# Sheet1.net
KiCad netlist of a schematic drawn in Altium Designer
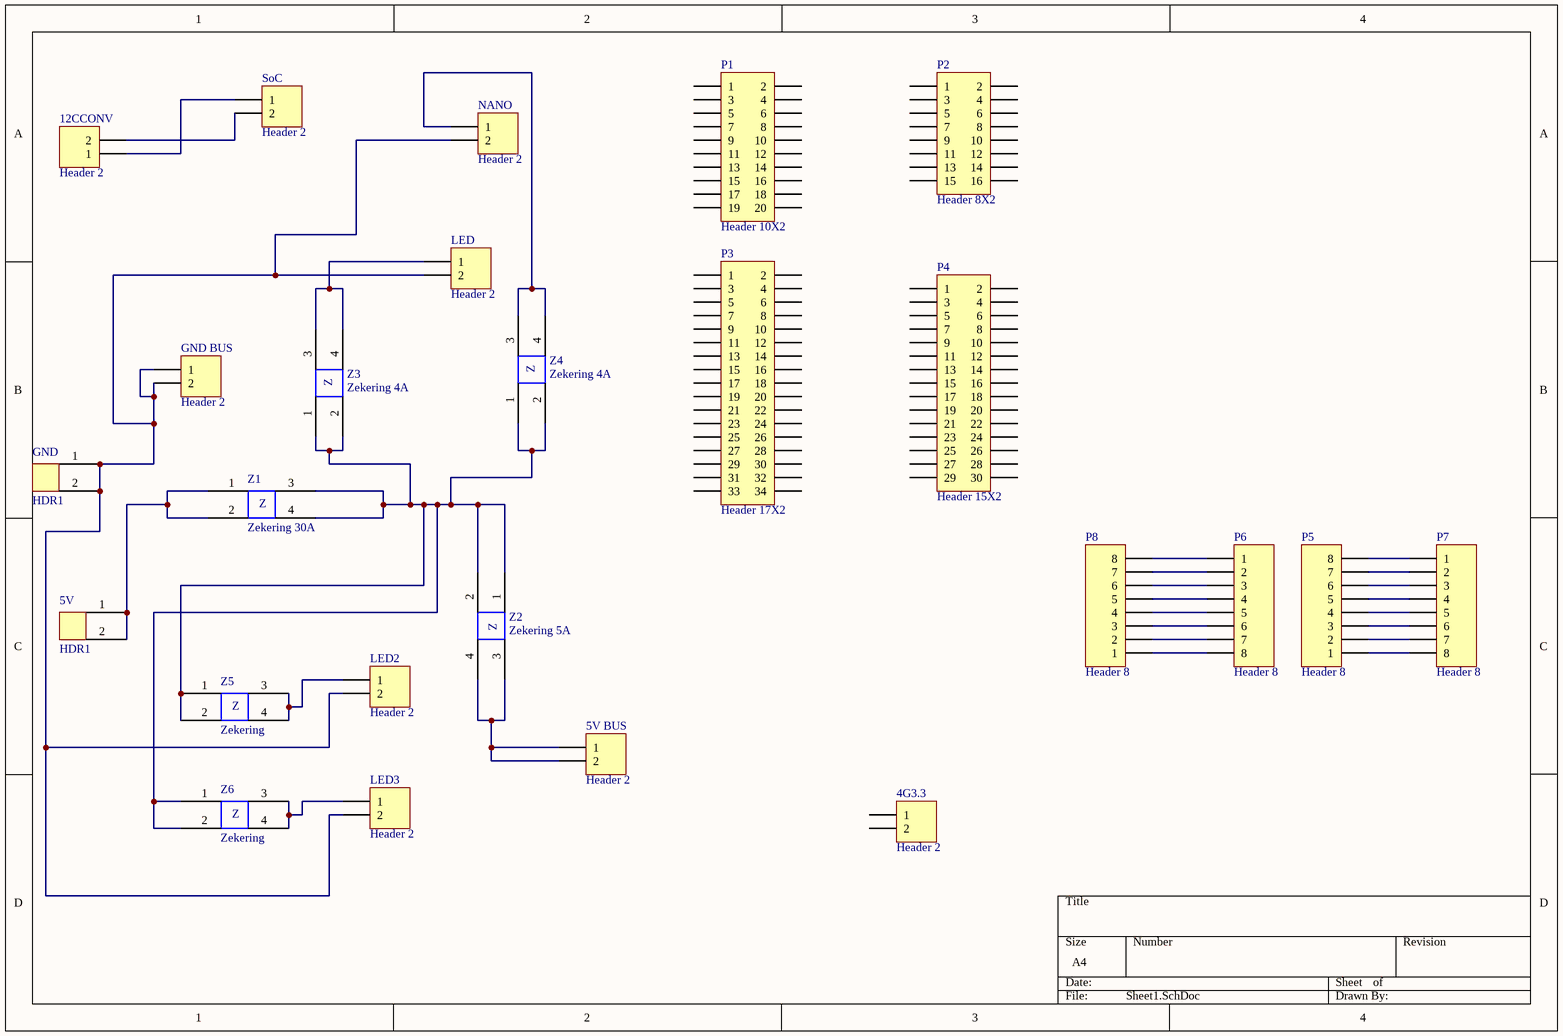
[diagram p0: Sheet1.SchDoc]

(export (version "E")
  (design (tool "Eeschema 10.0.6"))
  (components
    (comp (ref "4G3.3")
      (value "Header 2")
      (footprint "HDR1X2")
      (description "Header, 2-Pin")
      (fields (field (name "PUBLISHER") "Altium Limited"))
      (libsource (lib "Miscellaneous Connectors") (part "Header 2"))
    )
    (comp (ref "5V") (value "HDR1") (footprint "HDR1") (libsource (lib "Schlib1") (part "HDR1")))
    (comp (ref "5V BUS")
      (value "Header 2")
      (footprint "HDR2")
      (description "Header, 2-Pin")
      (fields (field (name "PUBLISHER") "Altium Limited"))
      (libsource (lib "Miscellaneous Connectors") (part "Header 2"))
    )
    (comp (ref "12CCONV")
      (value "Header 2")
      (footprint "HDR1X2")
      (description "Header, 2-Pin")
      (fields (field (name "PUBLISHER") "Altium Limited"))
      (libsource (lib "") (part "Header 2_1"))
    )
    (comp (ref "GND") (value "HDR1") (footprint "HDR1") (libsource (lib "Schlib1") (part "HDR1")))
    (comp (ref "GND BUS")
      (value "Header 2")
      (footprint "HDR2")
      (description "Header, 2-Pin")
      (fields (field (name "PUBLISHER") "Altium Limited"))
      (libsource (lib "Miscellaneous Connectors") (part "Header 2"))
    )
    (comp (ref "LED")
      (value "Header 2")
      (footprint "HDR2")
      (description "Header, 2-Pin")
      (fields (field (name "PUBLISHER") "Altium Limited"))
      (libsource (lib "Miscellaneous Connectors") (part "Header 2"))
    )
    (comp (ref "LED2")
      (value "Header 2")
      (footprint "HDR2")
      (description "Header, 2-Pin")
      (fields (field (name "PUBLISHER") "Altium Limited"))
      (libsource (lib "Miscellaneous Connectors") (part "Header 2"))
    )
    (comp (ref "LED3")
      (value "Header 2")
      (footprint "HDR2")
      (description "Header, 2-Pin")
      (fields (field (name "PUBLISHER") "Altium Limited"))
      (libsource (lib "Miscellaneous Connectors") (part "Header 2"))
    )
    (comp (ref "NANO")
      (value "Header 2")
      (footprint "HDR1X2")
      (description "Header, 2-Pin")
      (fields (field (name "PUBLISHER") "Altium Limited"))
      (libsource (lib "Miscellaneous Connectors") (part "Header 2"))
    )
    (comp (ref "P1")
      (value "Header 10X2")
      (footprint "hdr10x2")
      (description "Header, 10-Pin, Dual row")
      (fields (field (name "PUBLISHER") "Altium Limited"))
      (libsource (lib "Miscellaneous Connectors") (part "Header 10X2"))
    )
    (comp (ref "P2")
      (value "Header 8X2")
      (footprint "hdr8x2")
      (description "Header, 8-Pin, Dual row")
      (fields (field (name "PUBLISHER") "Altium Limited"))
      (libsource (lib "Miscellaneous Connectors") (part "Header 8X2"))
    )
    (comp (ref "P3")
      (value "Header 17X2")
      (footprint "hdr17x2")
      (description "Header, 17-Pin, Dual row")
      (fields (field (name "PUBLISHER") "Altium Limited"))
      (libsource (lib "Miscellaneous Connectors") (part "Header 17X2"))
    )
    (comp (ref "P4")
      (value "Header 15X2")
      (footprint "hdr15x2")
      (description "Header, 15-Pin, Dual row")
      (fields (field (name "PUBLISHER") "Altium Limited"))
      (libsource (lib "Miscellaneous Connectors") (part "Header 15X2"))
    )
    (comp (ref "P5")
      (value "Header 8")
      (footprint "HDR8")
      (description "Header, 8-Pin")
      (fields (field (name "PUBLISHER") "Altium Limited"))
      (libsource (lib "") (part "Header 8_1"))
    )
    (comp (ref "P6")
      (value "Header 8")
      (footprint "HDR8")
      (description "Header, 8-Pin")
      (fields (field (name "PUBLISHER") "Altium Limited"))
      (libsource (lib "Miscellaneous Connectors") (part "Header 8"))
    )
    (comp (ref "P7")
      (value "Header 8")
      (footprint "HDR8")
      (description "Header, 8-Pin")
      (fields (field (name "PUBLISHER") "Altium Limited"))
      (libsource (lib "Miscellaneous Connectors") (part "Header 8"))
    )
    (comp (ref "P8")
      (value "Header 8")
      (footprint "HDR8")
      (description "Header, 8-Pin")
      (fields (field (name "PUBLISHER") "Altium Limited"))
      (libsource (lib "") (part "Header 8_1"))
    )
    (comp (ref "SoC")
      (value "Header 2")
      (footprint "HDR1X2")
      (description "Header, 2-Pin")
      (fields (field (name "PUBLISHER") "Altium Limited"))
      (libsource (lib "Miscellaneous Connectors") (part "Header 2"))
    )
    (comp (ref "Z1")
      (value "Zekering 30A")
      (footprint "Zekering")
      (libsource (lib "Schlib1") (part "Zekering"))
    )
    (comp (ref "Z2")
      (value "Zekering 5A")
      (footprint "Zekering")
      (libsource (lib "Schlib1") (part "Zekering"))
    )
    (comp (ref "Z3")
      (value "Zekering 4A")
      (footprint "Zekering")
      (libsource (lib "Schlib1") (part "Zekering"))
    )
    (comp (ref "Z4")
      (value "Zekering 4A")
      (footprint "Zekering")
      (libsource (lib "Schlib1") (part "Zekering"))
    )
    (comp (ref "Z5") (value "Zekering") (footprint "Zekering") (libsource (lib "Schlib1") (part "Zekering")))
    (comp (ref "Z6") (value "Zekering") (footprint "Zekering") (libsource (lib "Schlib1") (part "Zekering")))
  )
  (nets
    (net (code "1") (name "Net-(5V-8)") (class "Default")
      (node (ref "5V") (pin "1") (pinfunction "8_1") (pintype "passive"))
      (node (ref "5V") (pin "2") (pinfunction "2_2") (pintype "passive"))
      (node (ref "Z1") (pin "1") (pinfunction "3_1") (pintype "passive"))
      (node (ref "Z1") (pin "2") (pinfunction "4_2") (pintype "passive"))
    )
    (net (code "2") (name "Net-(12CCONV-Pad1)") (class "Default")
      (node (ref "12CCONV") (pin "1") (pinfunction "1_1") (pintype "passive"))
      (node (ref "SoC") (pin "1") (pinfunction "1_1") (pintype "passive"))
    )
    (net (code "3") (name "Net-(12CCONV-Pad2)") (class "Default")
      (node (ref "12CCONV") (pin "2") (pinfunction "2_2") (pintype "passive"))
      (node (ref "SoC") (pin "2") (pinfunction "2_2") (pintype "passive"))
    )
    (net (code "4") (name "Net-(GND-8)") (class "Default")
      (node (ref "GND") (pin "1") (pinfunction "8_1") (pintype "passive"))
      (node (ref "GND") (pin "2") (pinfunction "2_2") (pintype "passive"))
      (node (ref "GND BUS") (pin "1") (pinfunction "1_1") (pintype "passive"))
      (node (ref "GND BUS") (pin "2") (pinfunction "2_2") (pintype "passive"))
      (node (ref "LED") (pin "2") (pinfunction "2_2") (pintype "passive"))
      (node (ref "LED2") (pin "2") (pinfunction "2_2") (pintype "passive"))
      (node (ref "LED3") (pin "2") (pinfunction "2_2") (pintype "passive"))
      (node (ref "NANO") (pin "2") (pinfunction "2_2") (pintype "passive"))
    )
    (net (code "5") (name "Net-(P5-Pad1)") (class "Default")
      (node (ref "P5") (pin "1") (pinfunction "1_1") (pintype "passive"))
      (node (ref "P7") (pin "8") (pinfunction "8_8") (pintype "passive"))
    )
    (net (code "6") (name "Net-(P5-Pad2)") (class "Default")
      (node (ref "P5") (pin "2") (pinfunction "2_2") (pintype "passive"))
      (node (ref "P7") (pin "7") (pinfunction "7_7") (pintype "passive"))
    )
    (net (code "7") (name "Net-(P5-Pad3)") (class "Default")
      (node (ref "P5") (pin "3") (pinfunction "3_3") (pintype "passive"))
      (node (ref "P7") (pin "6") (pinfunction "6_6") (pintype "passive"))
    )
    (net (code "8") (name "Net-(P5-Pad4)") (class "Default")
      (node (ref "P5") (pin "4") (pinfunction "4_4") (pintype "passive"))
      (node (ref "P7") (pin "5") (pinfunction "5_5") (pintype "passive"))
    )
    (net (code "9") (name "Net-(P5-Pad5)") (class "Default")
      (node (ref "P5") (pin "5") (pinfunction "5_5") (pintype "passive"))
      (node (ref "P7") (pin "4") (pinfunction "4_4") (pintype "passive"))
    )
    (net (code "10") (name "Net-(P5-Pad6)") (class "Default")
      (node (ref "P5") (pin "6") (pinfunction "6_6") (pintype "passive"))
      (node (ref "P7") (pin "3") (pinfunction "3_3") (pintype "passive"))
    )
    (net (code "11") (name "Net-(P5-Pad7)") (class "Default")
      (node (ref "P5") (pin "7") (pinfunction "7_7") (pintype "passive"))
      (node (ref "P7") (pin "2") (pinfunction "2_2") (pintype "passive"))
    )
    (net (code "12") (name "Net-(P5-Pad8)") (class "Default")
      (node (ref "P5") (pin "8") (pinfunction "8_8") (pintype "passive"))
      (node (ref "P7") (pin "1") (pinfunction "1_1") (pintype "passive"))
    )
    (net (code "13") (name "Net-(P6-Pad1)") (class "Default")
      (node (ref "P6") (pin "1") (pinfunction "1_1") (pintype "passive"))
      (node (ref "P8") (pin "8") (pinfunction "8_8") (pintype "passive"))
    )
    (net (code "14") (name "Net-(P6-Pad2)") (class "Default")
      (node (ref "P6") (pin "2") (pinfunction "2_2") (pintype "passive"))
      (node (ref "P8") (pin "7") (pinfunction "7_7") (pintype "passive"))
    )
    (net (code "15") (name "Net-(P6-Pad3)") (class "Default")
      (node (ref "P6") (pin "3") (pinfunction "3_3") (pintype "passive"))
      (node (ref "P8") (pin "6") (pinfunction "6_6") (pintype "passive"))
    )
    (net (code "16") (name "Net-(P6-Pad4)") (class "Default")
      (node (ref "P6") (pin "4") (pinfunction "4_4") (pintype "passive"))
      (node (ref "P8") (pin "5") (pinfunction "5_5") (pintype "passive"))
    )
    (net (code "17") (name "Net-(P6-Pad5)") (class "Default")
      (node (ref "P6") (pin "5") (pinfunction "5_5") (pintype "passive"))
      (node (ref "P8") (pin "4") (pinfunction "4_4") (pintype "passive"))
    )
    (net (code "18") (name "Net-(P6-Pad6)") (class "Default")
      (node (ref "P6") (pin "6") (pinfunction "6_6") (pintype "passive"))
      (node (ref "P8") (pin "3") (pinfunction "3_3") (pintype "passive"))
    )
    (net (code "19") (name "Net-(P6-Pad7)") (class "Default")
      (node (ref "P6") (pin "7") (pinfunction "7_7") (pintype "passive"))
      (node (ref "P8") (pin "2") (pinfunction "2_2") (pintype "passive"))
    )
    (net (code "20") (name "Net-(P6-Pad8)") (class "Default")
      (node (ref "P6") (pin "8") (pinfunction "8_8") (pintype "passive"))
      (node (ref "P8") (pin "1") (pinfunction "1_1") (pintype "passive"))
    )
    (net (code "21") (name "Net-(Z1-5)") (class "Default")
      (node (ref "Z1") (pin "3") (pinfunction "5_3") (pintype "passive"))
      (node (ref "Z1") (pin "4") (pinfunction "6_4") (pintype "passive"))
      (node (ref "Z2") (pin "1") (pinfunction "3_1") (pintype "passive"))
      (node (ref "Z2") (pin "2") (pinfunction "4_2") (pintype "passive"))
      (node (ref "Z3") (pin "1") (pinfunction "3_1") (pintype "passive"))
      (node (ref "Z3") (pin "2") (pinfunction "4_2") (pintype "passive"))
      (node (ref "Z4") (pin "1") (pinfunction "3_1") (pintype "passive"))
      (node (ref "Z4") (pin "2") (pinfunction "4_2") (pintype "passive"))
      (node (ref "Z5") (pin "1") (pinfunction "3_1") (pintype "passive"))
      (node (ref "Z5") (pin "2") (pinfunction "4_2") (pintype "passive"))
      (node (ref "Z6") (pin "1") (pinfunction "3_1") (pintype "passive"))
      (node (ref "Z6") (pin "2") (pinfunction "4_2") (pintype "passive"))
    )
    (net (code "22") (name "Net-(Z2-5)") (class "Default")
      (node (ref "5V BUS") (pin "1") (pinfunction "1_1") (pintype "passive"))
      (node (ref "5V BUS") (pin "2") (pinfunction "2_2") (pintype "passive"))
      (node (ref "Z2") (pin "3") (pinfunction "5_3") (pintype "passive"))
      (node (ref "Z2") (pin "4") (pinfunction "6_4") (pintype "passive"))
    )
    (net (code "23") (name "Net-(Z3-5)") (class "Default")
      (node (ref "LED") (pin "1") (pinfunction "1_1") (pintype "passive"))
      (node (ref "Z3") (pin "3") (pinfunction "5_3") (pintype "passive"))
      (node (ref "Z3") (pin "4") (pinfunction "6_4") (pintype "passive"))
    )
    (net (code "24") (name "Net-(Z4-5)") (class "Default")
      (node (ref "NANO") (pin "1") (pinfunction "1_1") (pintype "passive"))
      (node (ref "Z4") (pin "3") (pinfunction "5_3") (pintype "passive"))
      (node (ref "Z4") (pin "4") (pinfunction "6_4") (pintype "passive"))
    )
    (net (code "25") (name "Net-(Z5-5)") (class "Default")
      (node (ref "LED2") (pin "1") (pinfunction "1_1") (pintype "passive"))
      (node (ref "Z5") (pin "3") (pinfunction "5_3") (pintype "passive"))
      (node (ref "Z5") (pin "4") (pinfunction "6_4") (pintype "passive"))
    )
    (net (code "26") (name "Net-(Z6-5)") (class "Default")
      (node (ref "LED3") (pin "1") (pinfunction "1_1") (pintype "passive"))
      (node (ref "Z6") (pin "3") (pinfunction "5_3") (pintype "passive"))
      (node (ref "Z6") (pin "4") (pinfunction "6_4") (pintype "passive"))
    )
    (net (code "27") (name "unconnected-(4G3.3-Pad1)") (class "Default")
      (node (ref "4G3.3") (pin "1") (pinfunction "1_1") (pintype "passive"))
    )
    (net (code "28") (name "unconnected-(4G3.3-Pad2)") (class "Default")
      (node (ref "4G3.3") (pin "2") (pinfunction "2_2") (pintype "passive"))
    )
    (net (code "29") (name "unconnected-(P1-Pad1)") (class "Default")
      (node (ref "P1") (pin "1") (pinfunction "1_1") (pintype "passive"))
    )
    (net (code "30") (name "unconnected-(P1-Pad2)") (class "Default")
      (node (ref "P1") (pin "2") (pinfunction "2_2") (pintype "passive"))
    )
    (net (code "31") (name "unconnected-(P1-Pad3)") (class "Default")
      (node (ref "P1") (pin "3") (pinfunction "3_3") (pintype "passive"))
    )
    (net (code "32") (name "unconnected-(P1-Pad4)") (class "Default")
      (node (ref "P1") (pin "4") (pinfunction "4_4") (pintype "passive"))
    )
    (net (code "33") (name "unconnected-(P1-Pad5)") (class "Default")
      (node (ref "P1") (pin "5") (pinfunction "5_5") (pintype "passive"))
    )
    (net (code "34") (name "unconnected-(P1-Pad6)") (class "Default")
      (node (ref "P1") (pin "6") (pinfunction "6_6") (pintype "passive"))
    )
    (net (code "35") (name "unconnected-(P1-Pad7)") (class "Default")
      (node (ref "P1") (pin "7") (pinfunction "7_7") (pintype "passive"))
    )
    (net (code "36") (name "unconnected-(P1-Pad8)") (class "Default")
      (node (ref "P1") (pin "8") (pinfunction "8_8") (pintype "passive"))
    )
    (net (code "37") (name "unconnected-(P1-Pad9)") (class "Default")
      (node (ref "P1") (pin "9") (pinfunction "9_9") (pintype "passive"))
    )
    (net (code "38") (name "unconnected-(P1-Pad10)") (class "Default")
      (node (ref "P1") (pin "10") (pinfunction "10_10") (pintype "passive"))
    )
    (net (code "39") (name "unconnected-(P1-Pad11)") (class "Default")
      (node (ref "P1") (pin "11") (pinfunction "11_11") (pintype "passive"))
    )
    (net (code "40") (name "unconnected-(P1-Pad12)") (class "Default")
      (node (ref "P1") (pin "12") (pinfunction "12_12") (pintype "passive"))
    )
    (net (code "41") (name "unconnected-(P1-Pad13)") (class "Default")
      (node (ref "P1") (pin "13") (pinfunction "13_13") (pintype "passive"))
    )
    (net (code "42") (name "unconnected-(P1-Pad14)") (class "Default")
      (node (ref "P1") (pin "14") (pinfunction "14_14") (pintype "passive"))
    )
    (net (code "43") (name "unconnected-(P1-Pad15)") (class "Default")
      (node (ref "P1") (pin "15") (pinfunction "15_15") (pintype "passive"))
    )
    (net (code "44") (name "unconnected-(P1-Pad16)") (class "Default")
      (node (ref "P1") (pin "16") (pinfunction "16_16") (pintype "passive"))
    )
    (net (code "45") (name "unconnected-(P1-Pad17)") (class "Default")
      (node (ref "P1") (pin "17") (pinfunction "17_17") (pintype "passive"))
    )
    (net (code "46") (name "unconnected-(P1-Pad18)") (class "Default")
      (node (ref "P1") (pin "18") (pinfunction "18_18") (pintype "passive"))
    )
    (net (code "47") (name "unconnected-(P1-Pad19)") (class "Default")
      (node (ref "P1") (pin "19") (pinfunction "19_19") (pintype "passive"))
    )
    (net (code "48") (name "unconnected-(P1-Pad20)") (class "Default")
      (node (ref "P1") (pin "20") (pinfunction "20_20") (pintype "passive"))
    )
    (net (code "49") (name "unconnected-(P2-Pad1)") (class "Default")
      (node (ref "P2") (pin "1") (pinfunction "1_1") (pintype "passive"))
    )
    (net (code "50") (name "unconnected-(P2-Pad2)") (class "Default")
      (node (ref "P2") (pin "2") (pinfunction "2_2") (pintype "passive"))
    )
    (net (code "51") (name "unconnected-(P2-Pad3)") (class "Default")
      (node (ref "P2") (pin "3") (pinfunction "3_3") (pintype "passive"))
    )
    (net (code "52") (name "unconnected-(P2-Pad4)") (class "Default")
      (node (ref "P2") (pin "4") (pinfunction "4_4") (pintype "passive"))
    )
    (net (code "53") (name "unconnected-(P2-Pad5)") (class "Default")
      (node (ref "P2") (pin "5") (pinfunction "5_5") (pintype "passive"))
    )
    (net (code "54") (name "unconnected-(P2-Pad6)") (class "Default")
      (node (ref "P2") (pin "6") (pinfunction "6_6") (pintype "passive"))
    )
    (net (code "55") (name "unconnected-(P2-Pad7)") (class "Default")
      (node (ref "P2") (pin "7") (pinfunction "7_7") (pintype "passive"))
    )
    (net (code "56") (name "unconnected-(P2-Pad8)") (class "Default")
      (node (ref "P2") (pin "8") (pinfunction "8_8") (pintype "passive"))
    )
    (net (code "57") (name "unconnected-(P2-Pad9)") (class "Default")
      (node (ref "P2") (pin "9") (pinfunction "9_9") (pintype "passive"))
    )
    (net (code "58") (name "unconnected-(P2-Pad10)") (class "Default")
      (node (ref "P2") (pin "10") (pinfunction "10_10") (pintype "passive"))
    )
    (net (code "59") (name "unconnected-(P2-Pad11)") (class "Default")
      (node (ref "P2") (pin "11") (pinfunction "11_11") (pintype "passive"))
    )
    (net (code "60") (name "unconnected-(P2-Pad12)") (class "Default")
      (node (ref "P2") (pin "12") (pinfunction "12_12") (pintype "passive"))
    )
    (net (code "61") (name "unconnected-(P2-Pad13)") (class "Default")
      (node (ref "P2") (pin "13") (pinfunction "13_13") (pintype "passive"))
    )
    (net (code "62") (name "unconnected-(P2-Pad14)") (class "Default")
      (node (ref "P2") (pin "14") (pinfunction "14_14") (pintype "passive"))
    )
    (net (code "63") (name "unconnected-(P2-Pad15)") (class "Default")
      (node (ref "P2") (pin "15") (pinfunction "15_15") (pintype "passive"))
    )
    (net (code "64") (name "unconnected-(P2-Pad16)") (class "Default")
      (node (ref "P2") (pin "16") (pinfunction "16_16") (pintype "passive"))
    )
    (net (code "65") (name "unconnected-(P3-Pad1)") (class "Default")
      (node (ref "P3") (pin "1") (pinfunction "1_1") (pintype "passive"))
    )
    (net (code "66") (name "unconnected-(P3-Pad2)") (class "Default")
      (node (ref "P3") (pin "2") (pinfunction "2_2") (pintype "passive"))
    )
    (net (code "67") (name "unconnected-(P3-Pad3)") (class "Default")
      (node (ref "P3") (pin "3") (pinfunction "3_3") (pintype "passive"))
    )
    (net (code "68") (name "unconnected-(P3-Pad4)") (class "Default")
      (node (ref "P3") (pin "4") (pinfunction "4_4") (pintype "passive"))
    )
    (net (code "69") (name "unconnected-(P3-Pad5)") (class "Default")
      (node (ref "P3") (pin "5") (pinfunction "5_5") (pintype "passive"))
    )
    (net (code "70") (name "unconnected-(P3-Pad6)") (class "Default")
      (node (ref "P3") (pin "6") (pinfunction "6_6") (pintype "passive"))
    )
    (net (code "71") (name "unconnected-(P3-Pad7)") (class "Default")
      (node (ref "P3") (pin "7") (pinfunction "7_7") (pintype "passive"))
    )
    (net (code "72") (name "unconnected-(P3-Pad8)") (class "Default")
      (node (ref "P3") (pin "8") (pinfunction "8_8") (pintype "passive"))
    )
    (net (code "73") (name "unconnected-(P3-Pad9)") (class "Default")
      (node (ref "P3") (pin "9") (pinfunction "9_9") (pintype "passive"))
    )
    (net (code "74") (name "unconnected-(P3-Pad10)") (class "Default")
      (node (ref "P3") (pin "10") (pinfunction "10_10") (pintype "passive"))
    )
    (net (code "75") (name "unconnected-(P3-Pad11)") (class "Default")
      (node (ref "P3") (pin "11") (pinfunction "11_11") (pintype "passive"))
    )
    (net (code "76") (name "unconnected-(P3-Pad12)") (class "Default")
      (node (ref "P3") (pin "12") (pinfunction "12_12") (pintype "passive"))
    )
    (net (code "77") (name "unconnected-(P3-Pad13)") (class "Default")
      (node (ref "P3") (pin "13") (pinfunction "13_13") (pintype "passive"))
    )
    (net (code "78") (name "unconnected-(P3-Pad14)") (class "Default")
      (node (ref "P3") (pin "14") (pinfunction "14_14") (pintype "passive"))
    )
    (net (code "79") (name "unconnected-(P3-Pad15)") (class "Default")
      (node (ref "P3") (pin "15") (pinfunction "15_15") (pintype "passive"))
    )
    (net (code "80") (name "unconnected-(P3-Pad16)") (class "Default")
      (node (ref "P3") (pin "16") (pinfunction "16_16") (pintype "passive"))
    )
    (net (code "81") (name "unconnected-(P3-Pad17)") (class "Default")
      (node (ref "P3") (pin "17") (pinfunction "17_17") (pintype "passive"))
    )
    (net (code "82") (name "unconnected-(P3-Pad18)") (class "Default")
      (node (ref "P3") (pin "18") (pinfunction "18_18") (pintype "passive"))
    )
    (net (code "83") (name "unconnected-(P3-Pad19)") (class "Default")
      (node (ref "P3") (pin "19") (pinfunction "19_19") (pintype "passive"))
    )
    (net (code "84") (name "unconnected-(P3-Pad20)") (class "Default")
      (node (ref "P3") (pin "20") (pinfunction "20_20") (pintype "passive"))
    )
    (net (code "85") (name "unconnected-(P3-Pad21)") (class "Default")
      (node (ref "P3") (pin "21") (pinfunction "21_21") (pintype "passive"))
    )
    (net (code "86") (name "unconnected-(P3-Pad22)") (class "Default")
      (node (ref "P3") (pin "22") (pinfunction "22_22") (pintype "passive"))
    )
    (net (code "87") (name "unconnected-(P3-Pad23)") (class "Default")
      (node (ref "P3") (pin "23") (pinfunction "23_23") (pintype "passive"))
    )
    (net (code "88") (name "unconnected-(P3-Pad24)") (class "Default")
      (node (ref "P3") (pin "24") (pinfunction "24_24") (pintype "passive"))
    )
    (net (code "89") (name "unconnected-(P3-Pad25)") (class "Default")
      (node (ref "P3") (pin "25") (pinfunction "25_25") (pintype "passive"))
    )
    (net (code "90") (name "unconnected-(P3-Pad26)") (class "Default")
      (node (ref "P3") (pin "26") (pinfunction "26_26") (pintype "passive"))
    )
    (net (code "91") (name "unconnected-(P3-Pad27)") (class "Default")
      (node (ref "P3") (pin "27") (pinfunction "27_27") (pintype "passive"))
    )
    (net (code "92") (name "unconnected-(P3-Pad28)") (class "Default")
      (node (ref "P3") (pin "28") (pinfunction "28_28") (pintype "passive"))
    )
    (net (code "93") (name "unconnected-(P3-Pad29)") (class "Default")
      (node (ref "P3") (pin "29") (pinfunction "29_29") (pintype "passive"))
    )
    (net (code "94") (name "unconnected-(P3-Pad30)") (class "Default")
      (node (ref "P3") (pin "30") (pinfunction "30_30") (pintype "passive"))
    )
    (net (code "95") (name "unconnected-(P3-Pad31)") (class "Default")
      (node (ref "P3") (pin "31") (pinfunction "31_31") (pintype "passive"))
    )
    (net (code "96") (name "unconnected-(P3-Pad32)") (class "Default")
      (node (ref "P3") (pin "32") (pinfunction "32_32") (pintype "passive"))
    )
    (net (code "97") (name "unconnected-(P3-Pad33)") (class "Default")
      (node (ref "P3") (pin "33") (pinfunction "33_33") (pintype "passive"))
    )
    (net (code "98") (name "unconnected-(P3-Pad34)") (class "Default")
      (node (ref "P3") (pin "34") (pinfunction "34_34") (pintype "passive"))
    )
    (net (code "99") (name "unconnected-(P4-Pad1)") (class "Default")
      (node (ref "P4") (pin "1") (pinfunction "1_1") (pintype "passive"))
    )
    (net (code "100") (name "unconnected-(P4-Pad2)") (class "Default")
      (node (ref "P4") (pin "2") (pinfunction "2_2") (pintype "passive"))
    )
    (net (code "101") (name "unconnected-(P4-Pad3)") (class "Default")
      (node (ref "P4") (pin "3") (pinfunction "3_3") (pintype "passive"))
    )
    (net (code "102") (name "unconnected-(P4-Pad4)") (class "Default")
      (node (ref "P4") (pin "4") (pinfunction "4_4") (pintype "passive"))
    )
    (net (code "103") (name "unconnected-(P4-Pad5)") (class "Default")
      (node (ref "P4") (pin "5") (pinfunction "5_5") (pintype "passive"))
    )
    (net (code "104") (name "unconnected-(P4-Pad6)") (class "Default")
      (node (ref "P4") (pin "6") (pinfunction "6_6") (pintype "passive"))
    )
    (net (code "105") (name "unconnected-(P4-Pad7)") (class "Default")
      (node (ref "P4") (pin "7") (pinfunction "7_7") (pintype "passive"))
    )
    (net (code "106") (name "unconnected-(P4-Pad8)") (class "Default")
      (node (ref "P4") (pin "8") (pinfunction "8_8") (pintype "passive"))
    )
    (net (code "107") (name "unconnected-(P4-Pad9)") (class "Default")
      (node (ref "P4") (pin "9") (pinfunction "9_9") (pintype "passive"))
    )
    (net (code "108") (name "unconnected-(P4-Pad10)") (class "Default")
      (node (ref "P4") (pin "10") (pinfunction "10_10") (pintype "passive"))
    )
    (net (code "109") (name "unconnected-(P4-Pad11)") (class "Default")
      (node (ref "P4") (pin "11") (pinfunction "11_11") (pintype "passive"))
    )
    (net (code "110") (name "unconnected-(P4-Pad12)") (class "Default")
      (node (ref "P4") (pin "12") (pinfunction "12_12") (pintype "passive"))
    )
    (net (code "111") (name "unconnected-(P4-Pad13)") (class "Default")
      (node (ref "P4") (pin "13") (pinfunction "13_13") (pintype "passive"))
    )
    (net (code "112") (name "unconnected-(P4-Pad14)") (class "Default")
      (node (ref "P4") (pin "14") (pinfunction "14_14") (pintype "passive"))
    )
    (net (code "113") (name "unconnected-(P4-Pad15)") (class "Default")
      (node (ref "P4") (pin "15") (pinfunction "15_15") (pintype "passive"))
    )
    (net (code "114") (name "unconnected-(P4-Pad16)") (class "Default")
      (node (ref "P4") (pin "16") (pinfunction "16_16") (pintype "passive"))
    )
    (net (code "115") (name "unconnected-(P4-Pad17)") (class "Default")
      (node (ref "P4") (pin "17") (pinfunction "17_17") (pintype "passive"))
    )
    (net (code "116") (name "unconnected-(P4-Pad18)") (class "Default")
      (node (ref "P4") (pin "18") (pinfunction "18_18") (pintype "passive"))
    )
    (net (code "117") (name "unconnected-(P4-Pad19)") (class "Default")
      (node (ref "P4") (pin "19") (pinfunction "19_19") (pintype "passive"))
    )
    (net (code "118") (name "unconnected-(P4-Pad20)") (class "Default")
      (node (ref "P4") (pin "20") (pinfunction "20_20") (pintype "passive"))
    )
    (net (code "119") (name "unconnected-(P4-Pad21)") (class "Default")
      (node (ref "P4") (pin "21") (pinfunction "21_21") (pintype "passive"))
    )
    (net (code "120") (name "unconnected-(P4-Pad22)") (class "Default")
      (node (ref "P4") (pin "22") (pinfunction "22_22") (pintype "passive"))
    )
    (net (code "121") (name "unconnected-(P4-Pad23)") (class "Default")
      (node (ref "P4") (pin "23") (pinfunction "23_23") (pintype "passive"))
    )
    (net (code "122") (name "unconnected-(P4-Pad24)") (class "Default")
      (node (ref "P4") (pin "24") (pinfunction "24_24") (pintype "passive"))
    )
    (net (code "123") (name "unconnected-(P4-Pad25)") (class "Default")
      (node (ref "P4") (pin "25") (pinfunction "25_25") (pintype "passive"))
    )
    (net (code "124") (name "unconnected-(P4-Pad26)") (class "Default")
      (node (ref "P4") (pin "26") (pinfunction "26_26") (pintype "passive"))
    )
    (net (code "125") (name "unconnected-(P4-Pad27)") (class "Default")
      (node (ref "P4") (pin "27") (pinfunction "27_27") (pintype "passive"))
    )
    (net (code "126") (name "unconnected-(P4-Pad28)") (class "Default")
      (node (ref "P4") (pin "28") (pinfunction "28_28") (pintype "passive"))
    )
    (net (code "127") (name "unconnected-(P4-Pad29)") (class "Default")
      (node (ref "P4") (pin "29") (pinfunction "29_29") (pintype "passive"))
    )
    (net (code "128") (name "unconnected-(P4-Pad30)") (class "Default")
      (node (ref "P4") (pin "30") (pinfunction "30_30") (pintype "passive"))
    )
  )
)
